# CY8C4245LQI-BoB.net
KiCad netlist of a schematic drawn in Altium Designer
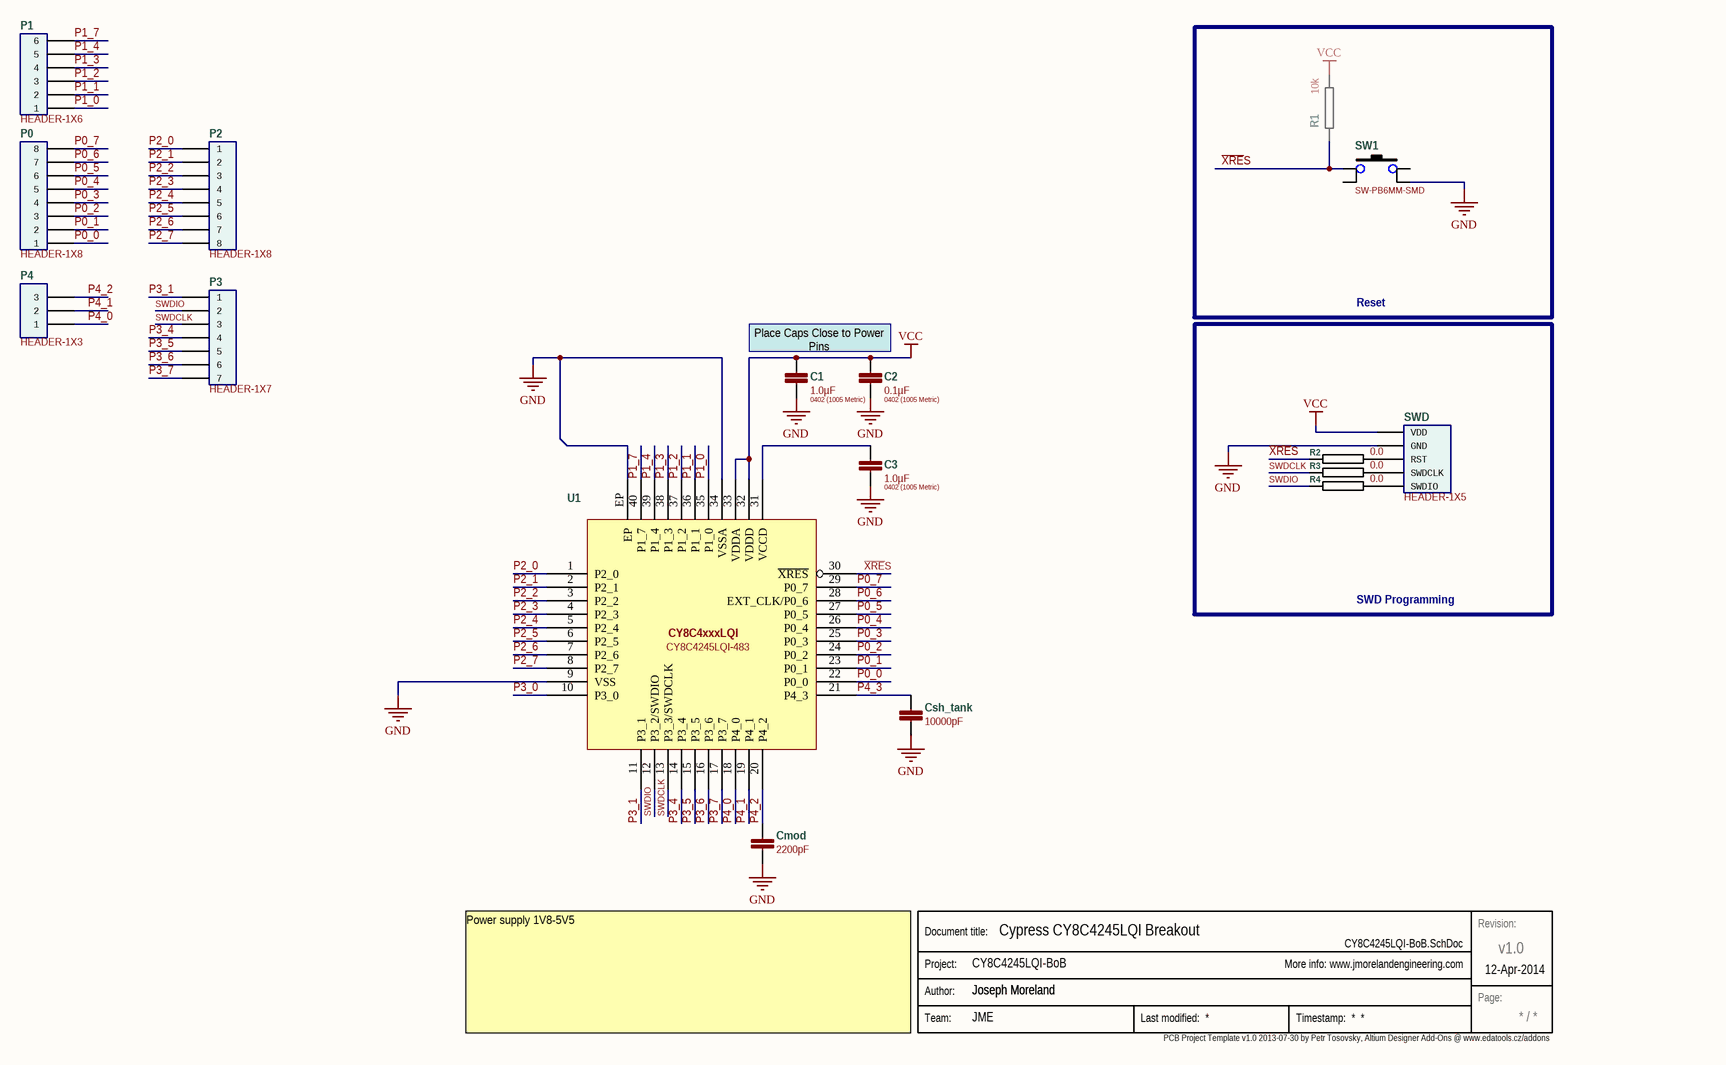
[diagram p0: CY8C4245LQI-BoB.SchDoc]

(export (version "E")
  (design (tool "Eeschema 10.0.6"))
  (components
    (comp (ref "C1")
      (value "1.0µF")
      (footprint "JCM-Capacitors:CAPC1005X06N")
      (description "CAP CER 1UF 10V 10% X5R 0402")
      (fields
        (field (name "MANUFACTURER") "Kemet")
        (field (name "MANUFACTURER PART NUMBER") "C0402C105K8PACTU")
        (field (name "PACKAGE / CASE") "0402 (1005 Metric)")
      )
      (libsource (lib "JCM-Capacitors") (part "C0402C105K8PACTU"))
    )
    (comp (ref "C2")
      (value "0.1µF")
      (footprint "CAPC1005X06N")
      (description "CAP CER 0.1UF 6.3V 10% X7R 0402")
      (fields
        (field (name "TOLERANCE") "±10%")
        (field (name "PACKAGE / CASE") "0402 (1005 Metric)")
        (field (name "MANUFACTURER") "Kemet")
      )
      (libsource (lib "JCM-Capacitors") (part "C0402C104K9RACTU"))
    )
    (comp (ref "C3")
      (value "1.0µF")
      (footprint "JCM-Capacitors:CAPC1005X06N")
      (description "CAP CER 1UF 10V 10% X5R 0402")
      (fields
        (field (name "MANUFACTURER") "Kemet")
        (field (name "MANUFACTURER PART NUMBER") "C0402C105K8PACTU")
        (field (name "PACKAGE / CASE") "0402 (1005 Metric)")
      )
      (libsource (lib "JCM-Capacitors") (part "C0402C105K8PACTU"))
    )
    (comp (ref "Cmod")
      (value "2200pF")
      (footprint "CAPC1005X06N")
      (description "CAP CER 2200PF 16V 10% X7R 0402")
      (fields (field (name "TOLERANCE") "±10%") (field (name "MANUFACTURER") "Kemet"))
      (libsource (lib "JCM-Capacitors") (part "C0402C222K4RACTU"))
    )
    (comp (ref "Csh_tank")
      (value "10000pF")
      (footprint "CAPC1005X06N")
      (description "CAP CER 10000PF 16V 10% X7R 0402")
      (fields
        (field (name "MANUFACTURER") "Kemet")
        (field (name "MANUFACTURER PART NUMBER") "C0402C103K4RACTU")
      )
      (libsource (lib "JCM-Capacitors") (part "C0402C103K4RACTU"))
    )
    (comp (ref "P0")
      (value "HEADER-1X8")
      (footprint "HEADER-1X8-100MIL")
      (libsource (lib "JCM-Connectors") (part "HEADER-1X8-100MIL"))
    )
    (comp (ref "P1")
      (value "HEADER-1X6")
      (footprint "HEADER-1X6-100MIL")
      (libsource (lib "JCM-Connectors") (part "HEADER-1X6-100MIL"))
    )
    (comp (ref "P2")
      (value "HEADER-1X8")
      (footprint "HEADER-1X8-100MIL")
      (libsource (lib "") (part "HEADER-1X8-100MIL_1"))
    )
    (comp (ref "P3")
      (value "HEADER-1X7")
      (footprint "HEADER-1X7-100MIL")
      (libsource (lib "JCM-Connectors") (part "HEADER-1X7-100MIL"))
    )
    (comp (ref "P4")
      (value "HEADER-1X3")
      (footprint "HEADER-1X3-100MIL")
      (libsource (lib "JCM-Connectors") (part "HEADER-1X3-100MIL"))
    )
    (comp (ref "R1")
      (value "10k")
      (footprint "RESC1005X04N")
      (description "RES 10.0K OHM 1/16W 1% 0402 SMD")
      (fields (field (name "MANUFACTURER_PART_NUMBER") "CRCW040210K0FKED") (field (name "POWER") "0.063"))
      (libsource (lib "JCM-Resistors") (part "CRCW040210K0FKED"))
    )
    (comp (ref "R2")
      (value "0.0")
      (footprint "RESC1005X04N")
      (description "RES 0.0 OHM 1/16W JUMP 0402 SMD")
      (fields
        (field (name "MANUFACTURER") "Vishay Dale")
        (field (name "MANUFACTURER PART NUMBER") "CRCW04020000Z0ED")
      )
      (libsource (lib "JCM-Resistors") (part "CRCW04020000Z0ED"))
    )
    (comp (ref "R3")
      (value "0.0")
      (footprint "RESC1005X04N")
      (description "RES 0.0 OHM 1/16W JUMP 0402 SMD")
      (fields
        (field (name "MANUFACTURER") "Vishay Dale")
        (field (name "MANUFACTURER PART NUMBER") "CRCW04020000Z0ED")
      )
      (libsource (lib "JCM-Resistors") (part "CRCW04020000Z0ED"))
    )
    (comp (ref "R4")
      (value "0.0")
      (footprint "RESC1005X04N")
      (description "RES 0.0 OHM 1/16W JUMP 0402 SMD")
      (fields
        (field (name "MANUFACTURER") "Vishay Dale")
        (field (name "MANUFACTURER PART NUMBER") "CRCW04020000Z0ED")
      )
      (libsource (lib "JCM-Resistors") (part "CRCW04020000Z0ED"))
    )
    (comp (ref "Stamp") (value "Stamp") (libsource (lib "ShieldsLib") (part "Stamp")))
    (comp (ref "SW1")
      (value "SW-PB6MM-SMD")
      (footprint "SW-PB-SMD")
      (description "PUSHBUTTON SWITCH 6MM SMD")
      (libsource (lib "JCM-Mechanical") (part "SW-PB6MM-SMD"))
    )
    (comp (ref "SWD")
      (value "HEADER-1X5")
      (footprint "HEADER-1X5-100MIL")
      (libsource (lib "JCM-Connectors") (part "CONN-1X5-100MIL-SWD-MiniProg"))
    )
    (comp (ref "U1")
      (value "CY8C4245LQI-483")
      (footprint "CY8C4xxxLQI")
      (description "PSOC4 IC MCU 32BIT 32KB FLASH 40QFN")
      (fields (field (name "MANUFACTURER") "Cypress Semiconductor Corp"))
      (libsource (lib "Cypress_PSOC4") (part "CY8C4245LQI"))
    )
  )
  (nets
    (net (code "1") (name "/P0_0") (class "Default")
      (node (ref "P0") (pin "1") (pinfunction "1_1") (pintype "passive"))
      (node (ref "U1") (pin "22") (pinfunction "P0_0_22") (pintype "passive"))
    )
    (net (code "2") (name "/P0_1") (class "Default")
      (node (ref "P0") (pin "2") (pinfunction "2_2") (pintype "passive"))
      (node (ref "U1") (pin "23") (pinfunction "P0_1_23") (pintype "passive"))
    )
    (net (code "3") (name "/P0_2") (class "Default")
      (node (ref "P0") (pin "3") (pinfunction "3_3") (pintype "passive"))
      (node (ref "U1") (pin "24") (pinfunction "P0_2_24") (pintype "passive"))
    )
    (net (code "4") (name "/P0_3") (class "Default")
      (node (ref "P0") (pin "4") (pinfunction "4_4") (pintype "passive"))
      (node (ref "U1") (pin "25") (pinfunction "P0_3_25") (pintype "passive"))
    )
    (net (code "5") (name "/P0_4") (class "Default")
      (node (ref "P0") (pin "5") (pinfunction "5_5") (pintype "passive"))
      (node (ref "U1") (pin "26") (pinfunction "P0_4_26") (pintype "passive"))
    )
    (net (code "6") (name "/P0_5") (class "Default")
      (node (ref "P0") (pin "6") (pinfunction "6_6") (pintype "passive"))
      (node (ref "U1") (pin "27") (pinfunction "P0_5_27") (pintype "passive"))
    )
    (net (code "7") (name "/P0_6") (class "Default")
      (node (ref "P0") (pin "7") (pinfunction "7_7") (pintype "passive"))
      (node (ref "U1") (pin "28") (pinfunction "EXT_CLK/P0_6_28") (pintype "passive"))
    )
    (net (code "8") (name "/P0_7") (class "Default")
      (node (ref "P0") (pin "8") (pinfunction "8_8") (pintype "passive"))
      (node (ref "U1") (pin "29") (pinfunction "P0_7_29") (pintype "passive"))
    )
    (net (code "9") (name "/P1_0") (class "Default")
      (node (ref "P1") (pin "1") (pinfunction "1_1") (pintype "passive"))
      (node (ref "U1") (pin "35") (pinfunction "P1_0_35") (pintype "passive"))
    )
    (net (code "10") (name "/P1_1") (class "Default")
      (node (ref "P1") (pin "2") (pinfunction "2_2") (pintype "passive"))
      (node (ref "U1") (pin "36") (pinfunction "P1_1_36") (pintype "passive"))
    )
    (net (code "11") (name "/P1_2") (class "Default")
      (node (ref "P1") (pin "3") (pinfunction "3_3") (pintype "passive"))
      (node (ref "U1") (pin "37") (pinfunction "P1_2_37") (pintype "passive"))
    )
    (net (code "12") (name "/P1_3") (class "Default")
      (node (ref "P1") (pin "4") (pinfunction "4_4") (pintype "passive"))
      (node (ref "U1") (pin "38") (pinfunction "P1_3_38") (pintype "passive"))
    )
    (net (code "13") (name "/P1_4") (class "Default")
      (node (ref "P1") (pin "5") (pinfunction "5_5") (pintype "passive"))
      (node (ref "U1") (pin "39") (pinfunction "P1_4_39") (pintype "passive"))
    )
    (net (code "14") (name "/P1_7") (class "Default")
      (node (ref "P1") (pin "6") (pinfunction "6_6") (pintype "passive"))
      (node (ref "U1") (pin "40") (pinfunction "P1_7_40") (pintype "passive"))
    )
    (net (code "15") (name "/P2_0") (class "Default")
      (node (ref "P2") (pin "1") (pinfunction "1_1") (pintype "passive"))
      (node (ref "U1") (pin "1") (pinfunction "P2_0_1") (pintype "passive"))
    )
    (net (code "16") (name "/P2_1") (class "Default")
      (node (ref "P2") (pin "2") (pinfunction "2_2") (pintype "passive"))
      (node (ref "U1") (pin "2") (pinfunction "P2_1_2") (pintype "passive"))
    )
    (net (code "17") (name "/P2_2") (class "Default")
      (node (ref "P2") (pin "3") (pinfunction "3_3") (pintype "passive"))
      (node (ref "U1") (pin "3") (pinfunction "P2_2_3") (pintype "passive"))
    )
    (net (code "18") (name "/P2_3") (class "Default")
      (node (ref "P2") (pin "4") (pinfunction "4_4") (pintype "passive"))
      (node (ref "U1") (pin "4") (pinfunction "P2_3_4") (pintype "passive"))
    )
    (net (code "19") (name "/P2_4") (class "Default")
      (node (ref "P2") (pin "5") (pinfunction "5_5") (pintype "passive"))
      (node (ref "U1") (pin "5") (pinfunction "P2_4_5") (pintype "passive"))
    )
    (net (code "20") (name "/P2_5") (class "Default")
      (node (ref "P2") (pin "6") (pinfunction "6_6") (pintype "passive"))
      (node (ref "U1") (pin "6") (pinfunction "P2_5_6") (pintype "passive"))
    )
    (net (code "21") (name "/P2_6") (class "Default")
      (node (ref "P2") (pin "7") (pinfunction "7_7") (pintype "passive"))
      (node (ref "U1") (pin "7") (pinfunction "P2_6_7") (pintype "passive"))
    )
    (net (code "22") (name "/P2_7") (class "Default")
      (node (ref "P2") (pin "8") (pinfunction "8_8") (pintype "passive"))
      (node (ref "U1") (pin "8") (pinfunction "P2_7_8") (pintype "passive"))
    )
    (net (code "23") (name "/P3_0") (class "Default")
      (node (ref "U1") (pin "10") (pinfunction "P3_0_10") (pintype "passive"))
    )
    (net (code "24") (name "/P3_1") (class "Default")
      (node (ref "P3") (pin "1") (pinfunction "1_1") (pintype "passive"))
      (node (ref "U1") (pin "11") (pinfunction "P3_1_11") (pintype "passive"))
    )
    (net (code "25") (name "/P3_4") (class "Default")
      (node (ref "P3") (pin "4") (pinfunction "4_4") (pintype "passive"))
      (node (ref "U1") (pin "14") (pinfunction "P3_4_14") (pintype "passive"))
    )
    (net (code "26") (name "/P3_5") (class "Default")
      (node (ref "P3") (pin "5") (pinfunction "5_5") (pintype "passive"))
      (node (ref "U1") (pin "15") (pinfunction "P3_5_15") (pintype "passive"))
    )
    (net (code "27") (name "/P3_6") (class "Default")
      (node (ref "P3") (pin "6") (pinfunction "6_6") (pintype "passive"))
      (node (ref "U1") (pin "16") (pinfunction "P3_6_16") (pintype "passive"))
    )
    (net (code "28") (name "/P3_7") (class "Default")
      (node (ref "P3") (pin "7") (pinfunction "7_7") (pintype "passive"))
      (node (ref "U1") (pin "17") (pinfunction "P3_7_17") (pintype "passive"))
    )
    (net (code "29") (name "/P4_0") (class "Default")
      (node (ref "P4") (pin "1") (pinfunction "1_1") (pintype "passive"))
      (node (ref "U1") (pin "18") (pinfunction "P4_0_18") (pintype "passive"))
    )
    (net (code "30") (name "/P4_1") (class "Default")
      (node (ref "P4") (pin "2") (pinfunction "2_2") (pintype "passive"))
      (node (ref "U1") (pin "19") (pinfunction "P4_1_19") (pintype "passive"))
    )
    (net (code "31") (name "/P4_2") (class "Default")
      (node (ref "Cmod") (pin "1") (pinfunction "1_1") (pintype "passive"))
      (node (ref "P4") (pin "3") (pinfunction "3_3") (pintype "passive"))
      (node (ref "U1") (pin "20") (pinfunction "P4_2_20") (pintype "passive"))
    )
    (net (code "32") (name "/P4_3") (class "Default")
      (node (ref "Csh_tank") (pin "1") (pinfunction "1_1") (pintype "passive"))
      (node (ref "U1") (pin "21") (pinfunction "P4_3_21") (pintype "passive"))
    )
    (net (code "33") (name "/SWDCLK") (class "Default")
      (node (ref "P3") (pin "3") (pinfunction "3_3") (pintype "passive"))
      (node (ref "R3") (pin "2") (pinfunction "2_2") (pintype "passive"))
      (node (ref "U1") (pin "13") (pinfunction "P3_3/SWDCLK_13") (pintype "passive"))
    )
    (net (code "34") (name "/SWDIO") (class "Default")
      (node (ref "P3") (pin "2") (pinfunction "2_2") (pintype "passive"))
      (node (ref "R4") (pin "2") (pinfunction "2_2") (pintype "passive"))
      (node (ref "U1") (pin "12") (pinfunction "P3_2/SWDIO_12") (pintype "passive"))
    )
    (net (code "35") (name "/~{XRE}S") (class "Default")
      (node (ref "R1") (pin "2") (pinfunction "2_2") (pintype "passive"))
      (node (ref "R2") (pin "2") (pinfunction "2_2") (pintype "passive"))
      (node (ref "SW1") (pin "1") (pintype "passive"))
      (node (ref "U1") (pin "30") (pinfunction "~{XRES}_30") (pintype "passive"))
    )
    (net (code "36") (name "GND") (class "Default")
      (node (ref "C1") (pin "2") (pinfunction "2_2") (pintype "passive"))
      (node (ref "C2") (pin "2") (pinfunction "2_2") (pintype "passive"))
      (node (ref "C3") (pin "2") (pinfunction "2_2") (pintype "passive"))
      (node (ref "Cmod") (pin "2") (pinfunction "2_2") (pintype "passive"))
      (node (ref "Csh_tank") (pin "2") (pinfunction "2_2") (pintype "passive"))
      (node (ref "SW1") (pin "4") (pintype "passive"))
      (node (ref "SWD") (pin "2") (pinfunction "GND_2") (pintype "passive"))
      (node (ref "U1") (pin "34") (pinfunction "VSSA_34") (pintype "passive"))
      (node (ref "U1") (pin "9") (pinfunction "VSS_9") (pintype "passive"))
      (node (ref "U1") (pin "EP") (pinfunction "EP_EP") (pintype "passive"))
    )
    (net (code "37") (name "Net-(SWD-RST)") (class "Default")
      (node (ref "R2") (pin "1") (pinfunction "1_1") (pintype "passive"))
      (node (ref "SWD") (pin "3") (pinfunction "RST_3") (pintype "passive"))
    )
    (net (code "38") (name "Net-(SWD-SWDCLK)") (class "Default")
      (node (ref "R3") (pin "1") (pinfunction "1_1") (pintype "passive"))
      (node (ref "SWD") (pin "4") (pinfunction "SWDCLK_4") (pintype "passive"))
    )
    (net (code "39") (name "Net-(SWD-SWDIO)") (class "Default")
      (node (ref "R4") (pin "1") (pinfunction "1_1") (pintype "passive"))
      (node (ref "SWD") (pin "5") (pinfunction "SWDIO_5") (pintype "passive"))
    )
    (net (code "40") (name "Net-(U1-VCCD)") (class "Default")
      (node (ref "C3") (pin "1") (pinfunction "1_1") (pintype "passive"))
      (node (ref "U1") (pin "31") (pinfunction "VCCD_31") (pintype "passive"))
    )
    (net (code "41") (name "VCC") (class "Default")
      (node (ref "C1") (pin "1") (pinfunction "1_1") (pintype "passive"))
      (node (ref "C2") (pin "1") (pinfunction "1_1") (pintype "passive"))
      (node (ref "R1") (pin "1") (pinfunction "1_1") (pintype "passive"))
      (node (ref "SWD") (pin "1") (pinfunction "VDD_1") (pintype "passive"))
      (node (ref "U1") (pin "32") (pinfunction "VDDD_32") (pintype "passive"))
      (node (ref "U1") (pin "33") (pinfunction "VDDA_33") (pintype "passive"))
    )
    (net (code "42") (name "unconnected-(SW1-Pad2)") (class "Default")
      (node (ref "SW1") (pin "2") (pintype "passive"))
    )
    (net (code "43") (name "unconnected-(SW1-Pad3)") (class "Default")
      (node (ref "SW1") (pin "3") (pintype "passive"))
    )
  )
)
